# time-twister.net
KiCad netlist of a schematic drawn in EAGLE
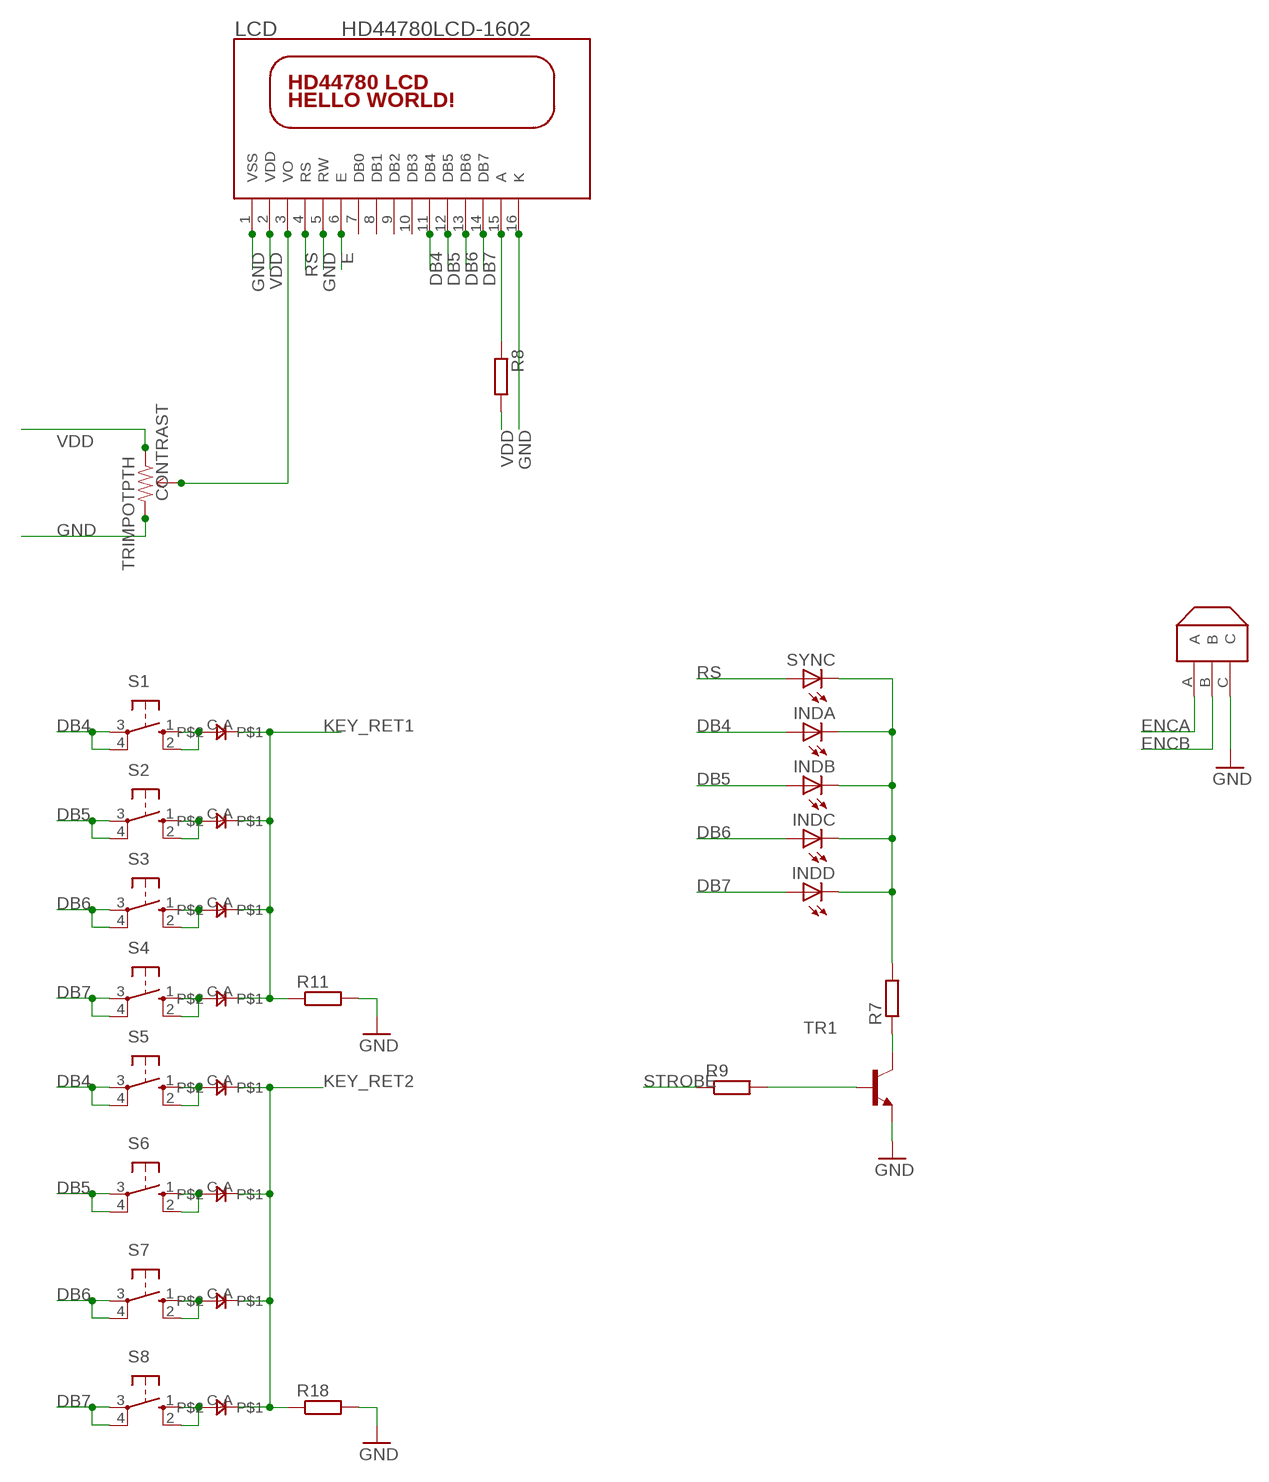
[diagram p0: schematic, sheet 1]
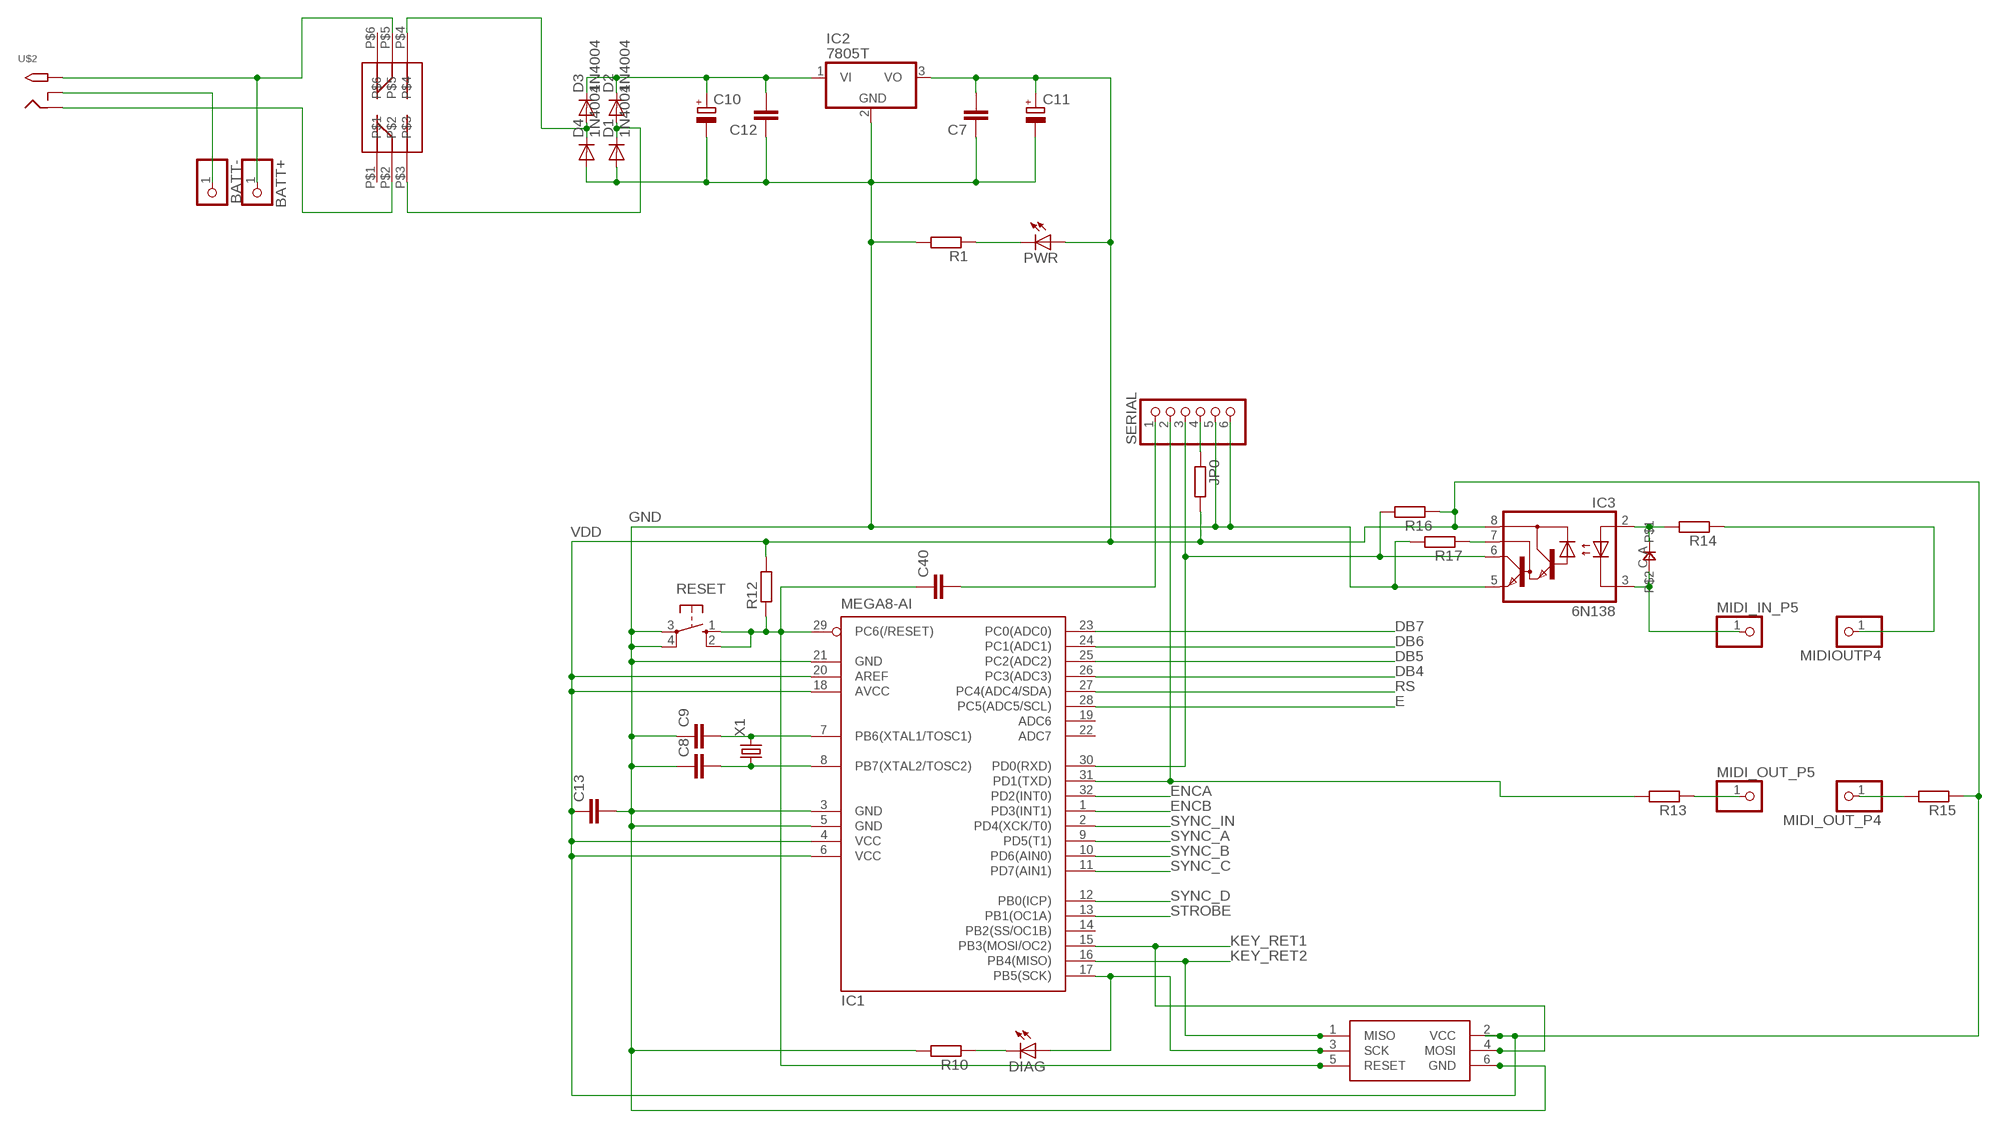
[diagram p1: schematic, sheet 2]
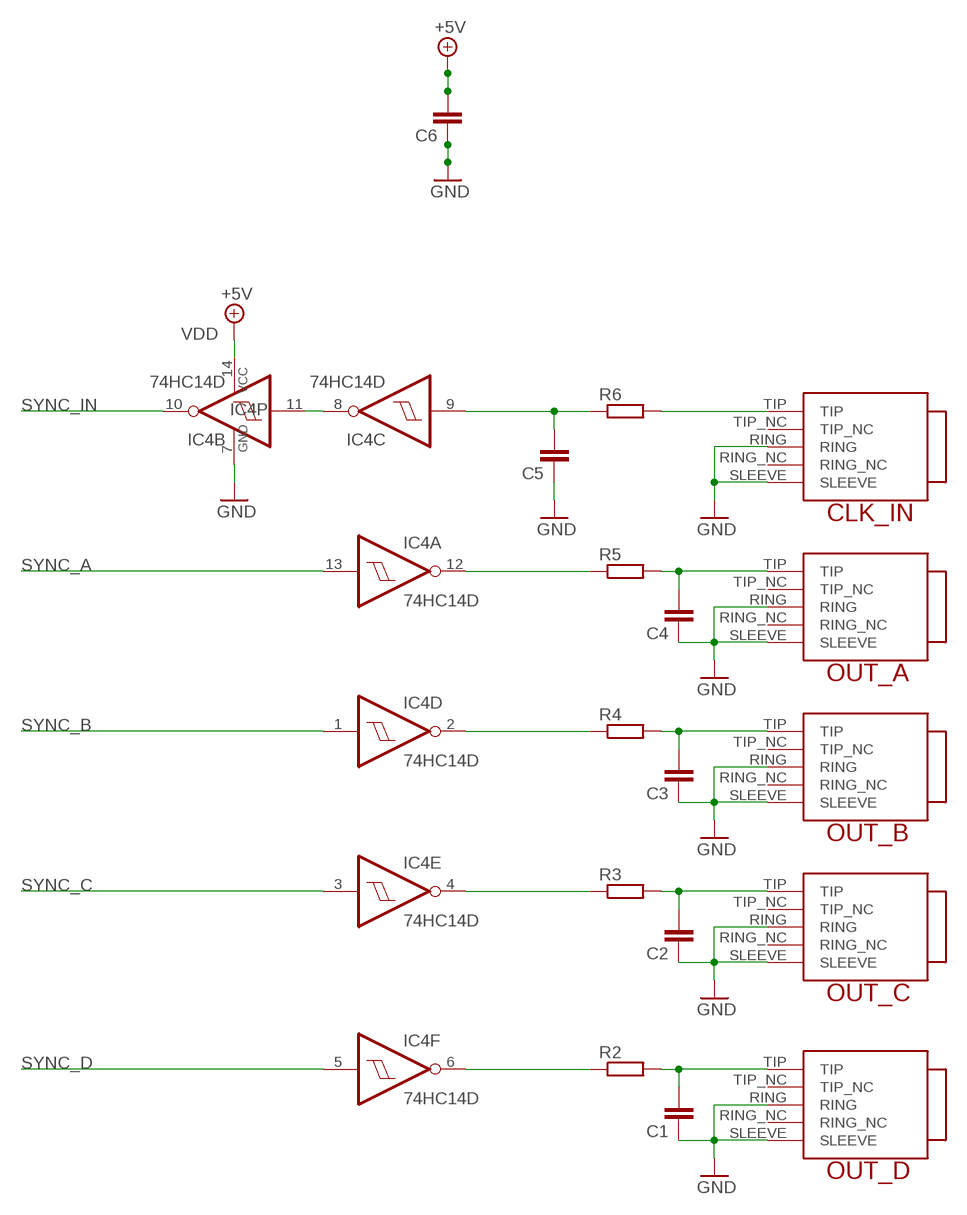
[diagram p2: schematic, sheet 3]

(export (version "E")
  (design (tool "Eeschema 10.0.6"))
  (components
    (comp (ref "C1")
      (value "C-EUC0805")
      (footprint "eagle-import:C0805")
      (libsource (lib "eagle-import") (part "C-EUC0805"))
    )
    (comp (ref "C2")
      (value "C-EUC0805")
      (footprint "eagle-import:C0805")
      (libsource (lib "eagle-import") (part "C-EUC0805"))
    )
    (comp (ref "C3")
      (value "C-EUC0805")
      (footprint "eagle-import:C0805")
      (libsource (lib "eagle-import") (part "C-EUC0805"))
    )
    (comp (ref "C4")
      (value "C-EUC0805")
      (footprint "eagle-import:C0805")
      (libsource (lib "eagle-import") (part "C-EUC0805"))
    )
    (comp (ref "C5")
      (value "C-EUC0805")
      (footprint "eagle-import:C0805")
      (libsource (lib "eagle-import") (part "C-EUC0805"))
    )
    (comp (ref "C6")
      (value "C-EUC0805")
      (footprint "eagle-import:C0805")
      (libsource (lib "eagle-import") (part "C-EUC0805"))
    )
    (comp (ref "CLK_IN")
      (value "TRUCONNECTJACK")
      (footprint "eagle-import:TRUCONNECTJACK")
      (libsource (lib "eagle-import") (part "TRUCONNECTJACK"))
    )
    (comp (ref "IC4")
      (value "74HC14D")
      (footprint "eagle-import:SO14")
      (libsource (lib "eagle-import") (part "7414DHC"))
    )
    (comp (ref "OUT_A")
      (value "TRUCONNECTJACK")
      (footprint "eagle-import:TRUCONNECTJACK")
      (libsource (lib "eagle-import") (part "TRUCONNECTJACK"))
    )
    (comp (ref "OUT_B")
      (value "TRUCONNECTJACK")
      (footprint "eagle-import:TRUCONNECTJACK")
      (libsource (lib "eagle-import") (part "TRUCONNECTJACK"))
    )
    (comp (ref "OUT_C")
      (value "TRUCONNECTJACK")
      (footprint "eagle-import:TRUCONNECTJACK")
      (libsource (lib "eagle-import") (part "TRUCONNECTJACK"))
    )
    (comp (ref "OUT_D")
      (value "TRUCONNECTJACK")
      (footprint "eagle-import:TRUCONNECTJACK")
      (libsource (lib "eagle-import") (part "TRUCONNECTJACK"))
    )
    (comp (ref "R2")
      (value "R-EU_M0805")
      (footprint "eagle-import:M0805")
      (libsource (lib "eagle-import") (part "R-EU_M0805"))
    )
    (comp (ref "R3")
      (value "R-EU_M0805")
      (footprint "eagle-import:M0805")
      (libsource (lib "eagle-import") (part "R-EU_M0805"))
    )
    (comp (ref "R4")
      (value "R-EU_M0805")
      (footprint "eagle-import:M0805")
      (libsource (lib "eagle-import") (part "R-EU_M0805"))
    )
    (comp (ref "R5")
      (value "R-EU_M0805")
      (footprint "eagle-import:M0805")
      (libsource (lib "eagle-import") (part "R-EU_M0805"))
    )
    (comp (ref "R6")
      (value "R-EU_M0805")
      (footprint "eagle-import:M0805")
      (libsource (lib "eagle-import") (part "R-EU_M0805"))
    )
    (comp (ref "CONTRAST")
      (value "TRIMPOTPTH")
      (footprint "eagle-import:TRIM_POT_PTH")
      (libsource (lib "eagle-import") (part "TRIMPOTPTH"))
    )
    (comp (ref "D5")
      (value "0805DIODE")
      (footprint "eagle-import:0805DIODE")
      (libsource (lib "eagle-import") (part "0805DIODE"))
    )
    (comp (ref "D6")
      (value "0805DIODE")
      (footprint "eagle-import:0805DIODE")
      (libsource (lib "eagle-import") (part "0805DIODE"))
    )
    (comp (ref "D7")
      (value "0805DIODE")
      (footprint "eagle-import:0805DIODE")
      (libsource (lib "eagle-import") (part "0805DIODE"))
    )
    (comp (ref "D8")
      (value "0805DIODE")
      (footprint "eagle-import:0805DIODE")
      (libsource (lib "eagle-import") (part "0805DIODE"))
    )
    (comp (ref "D10")
      (value "0805DIODE")
      (footprint "eagle-import:0805DIODE")
      (libsource (lib "eagle-import") (part "0805DIODE"))
    )
    (comp (ref "D11")
      (value "0805DIODE")
      (footprint "eagle-import:0805DIODE")
      (libsource (lib "eagle-import") (part "0805DIODE"))
    )
    (comp (ref "D12")
      (value "0805DIODE")
      (footprint "eagle-import:0805DIODE")
      (libsource (lib "eagle-import") (part "0805DIODE"))
    )
    (comp (ref "D13")
      (value "0805DIODE")
      (footprint "eagle-import:0805DIODE")
      (libsource (lib "eagle-import") (part "0805DIODE"))
    )
    (comp (ref "ENC1")
      (value "ENCODER")
      (footprint "eagle-import:ENCODER")
      (libsource (lib "eagle-import") (part "ENCODER"))
    )
    (comp (ref "INDA")
      (value "LED3MM")
      (footprint "eagle-import:LED3MM")
      (libsource (lib "eagle-import") (part "led_LED3MM"))
    )
    (comp (ref "INDB")
      (value "LED3MM")
      (footprint "eagle-import:LED3MM")
      (libsource (lib "eagle-import") (part "led_LED3MM"))
    )
    (comp (ref "INDC")
      (value "LED3MM")
      (footprint "eagle-import:LED3MM")
      (libsource (lib "eagle-import") (part "led_LED3MM"))
    )
    (comp (ref "INDD")
      (value "LED3MM")
      (footprint "eagle-import:LED3MM")
      (libsource (lib "eagle-import") (part "led_LED3MM"))
    )
    (comp (ref "LCD")
      (value "HD44780LCD-1602")
      (footprint "eagle-import:LCD1602")
      (libsource (lib "eagle-import") (part "HD44780LCD-1602"))
    )
    (comp (ref "R7")
      (value "R-EU_R0805")
      (footprint "eagle-import:R0805")
      (libsource (lib "eagle-import") (part "R-EU_R0805"))
    )
    (comp (ref "R8")
      (value "R-EU_R0805")
      (footprint "eagle-import:R0805")
      (libsource (lib "eagle-import") (part "R-EU_R0805"))
    )
    (comp (ref "R9")
      (value "R-EU_R0805")
      (footprint "eagle-import:R0805")
      (libsource (lib "eagle-import") (part "R-EU_R0805"))
    )
    (comp (ref "R11")
      (value "R-EU_R0805")
      (footprint "eagle-import:R0805")
      (libsource (lib "eagle-import") (part "R-EU_R0805"))
    )
    (comp (ref "R18")
      (value "R-EU_R0805")
      (footprint "eagle-import:R0805")
      (libsource (lib "eagle-import") (part "R-EU_R0805"))
    )
    (comp (ref "S1")
      (value "40-XX")
      (footprint "eagle-import:B3F-40XX")
      (fields (field (name "MF") "OMRON COMPONENTS USA") (field (name "MPN") "B3F-4000"))
      (libsource (lib "eagle-import") (part "40-XX"))
    )
    (comp (ref "S2")
      (value "40-XX")
      (footprint "eagle-import:B3F-40XX")
      (fields (field (name "MF") "OMRON COMPONENTS USA") (field (name "MPN") "B3F-4000"))
      (libsource (lib "eagle-import") (part "40-XX"))
    )
    (comp (ref "S3")
      (value "40-XX")
      (footprint "eagle-import:B3F-40XX")
      (fields (field (name "MF") "OMRON COMPONENTS USA") (field (name "MPN") "B3F-4000"))
      (libsource (lib "eagle-import") (part "40-XX"))
    )
    (comp (ref "S4")
      (value "40-XX")
      (footprint "eagle-import:B3F-40XX")
      (fields (field (name "MF") "OMRON COMPONENTS USA") (field (name "MPN") "B3F-4000"))
      (libsource (lib "eagle-import") (part "40-XX"))
    )
    (comp (ref "S5")
      (value "40-XX")
      (footprint "eagle-import:B3F-40XX")
      (fields (field (name "MF") "OMRON COMPONENTS USA") (field (name "MPN") "B3F-4000"))
      (libsource (lib "eagle-import") (part "40-XX"))
    )
    (comp (ref "S6")
      (value "40-XX")
      (footprint "eagle-import:B3F-40XX")
      (fields (field (name "MF") "OMRON COMPONENTS USA") (field (name "MPN") "B3F-4000"))
      (libsource (lib "eagle-import") (part "40-XX"))
    )
    (comp (ref "S7")
      (value "40-XX")
      (footprint "eagle-import:B3F-40XX")
      (fields (field (name "MF") "OMRON COMPONENTS USA") (field (name "MPN") "B3F-4000"))
      (libsource (lib "eagle-import") (part "40-XX"))
    )
    (comp (ref "S8")
      (value "40-XX")
      (footprint "eagle-import:B3F-40XX")
      (fields (field (name "MF") "OMRON COMPONENTS USA") (field (name "MPN") "B3F-4000"))
      (libsource (lib "eagle-import") (part "40-XX"))
    )
    (comp (ref "SYNC")
      (value "LED3MM")
      (footprint "eagle-import:LED3MM")
      (libsource (lib "eagle-import") (part "led_LED3MM"))
    )
    (comp (ref "TR1")
      (value "MMBT3904LT1-NPN-SOT23-BEC")
      (footprint "eagle-import:SOT23-BEC")
      (libsource (lib "eagle-import") (part "-NPN-SOT23-BECMMBT3904LT1"))
    )
    (comp (ref "BATT+")
      (value "HEADER-1X1")
      (footprint "eagle-import:1X01_OVAL")
      (libsource (lib "eagle-import") (part "HEADER-1X1"))
    )
    (comp (ref "BATT-")
      (value "HEADER-1X1")
      (footprint "eagle-import:1X01_OVAL")
      (libsource (lib "eagle-import") (part "HEADER-1X1"))
    )
    (comp (ref "C7")
      (value "C-EUC0805")
      (footprint "eagle-import:C0805")
      (libsource (lib "eagle-import") (part "C-EUC0805"))
    )
    (comp (ref "C8")
      (value "C-EUC0805")
      (footprint "eagle-import:C0805")
      (libsource (lib "eagle-import") (part "C-EUC0805"))
    )
    (comp (ref "C9")
      (value "C-EUC0805")
      (footprint "eagle-import:C0805")
      (libsource (lib "eagle-import") (part "C-EUC0805"))
    )
    (comp (ref "C10")
      (value "CPOL-EUE2.5-6")
      (footprint "eagle-import:E2,5-6")
      (libsource (lib "eagle-import") (part "CPOL-EUE2.5-6"))
    )
    (comp (ref "C11")
      (value "CPOL-EUE2.5-6")
      (footprint "eagle-import:E2,5-6")
      (libsource (lib "eagle-import") (part "CPOL-EUE2.5-6"))
    )
    (comp (ref "C12")
      (value "C-EUC0805")
      (footprint "eagle-import:C0805")
      (libsource (lib "eagle-import") (part "C-EUC0805"))
    )
    (comp (ref "C13")
      (value "C-EUC0805")
      (footprint "eagle-import:C0805")
      (libsource (lib "eagle-import") (part "C-EUC0805"))
    )
    (comp (ref "C40")
      (value "C-EUC0805")
      (footprint "eagle-import:C0805")
      (libsource (lib "eagle-import") (part "C-EUC0805"))
    )
    (comp (ref "D1")
      (value "1N4004")
      (footprint "eagle-import:DO-VERT")
      (libsource (lib "eagle-import") (part "1N4004"))
    )
    (comp (ref "D2")
      (value "1N4004")
      (footprint "eagle-import:DO-VERT")
      (libsource (lib "eagle-import") (part "1N4004"))
    )
    (comp (ref "D3")
      (value "1N4004")
      (footprint "eagle-import:DO-VERT")
      (libsource (lib "eagle-import") (part "1N4004"))
    )
    (comp (ref "D4")
      (value "1N4004")
      (footprint "eagle-import:DO-VERT")
      (libsource (lib "eagle-import") (part "1N4004"))
    )
    (comp (ref "D9")
      (value "0805DIODE")
      (footprint "eagle-import:0805DIODE")
      (libsource (lib "eagle-import") (part "0805DIODE"))
    )
    (comp (ref "DIAG")
      (value "LED3MM")
      (footprint "eagle-import:LED3MM")
      (libsource (lib "eagle-import") (part "led_LED3MM"))
    )
    (comp (ref "IC1")
      (value "MEGA8-AI")
      (footprint "eagle-import:TQFP32-08")
      (libsource (lib "eagle-import") (part "MEGA8-AI"))
    )
    (comp (ref "IC2")
      (value "7805T")
      (footprint "eagle-import:TO220H")
      (libsource (lib "eagle-import") (part "78T05"))
    )
    (comp (ref "IC3")
      (value "6N138")
      (footprint "eagle-import:DIL08")
      (libsource (lib "eagle-import") (part "6N138"))
    )
    (comp (ref "JP0")
      (value "R-EU_R0805")
      (footprint "eagle-import:R0805")
      (libsource (lib "eagle-import") (part "R-EU_R0805"))
    )
    (comp (ref "MIDIOUTP4")
      (value "HEADER-1X1")
      (footprint "eagle-import:1X01_OVAL")
      (libsource (lib "eagle-import") (part "HEADER-1X1"))
    )
    (comp (ref "MIDI_IN_P5")
      (value "HEADER-1X1")
      (footprint "eagle-import:1X01_OVAL")
      (libsource (lib "eagle-import") (part "HEADER-1X1"))
    )
    (comp (ref "MIDI_OUT_P4")
      (value "HEADER-1X1")
      (footprint "eagle-import:1X01_OVAL")
      (libsource (lib "eagle-import") (part "HEADER-1X1"))
    )
    (comp (ref "MIDI_OUT_P5")
      (value "HEADER-1X1")
      (footprint "eagle-import:1X01_OVAL")
      (libsource (lib "eagle-import") (part "HEADER-1X1"))
    )
    (comp (ref "ONOFF")
      (value "2P2T_LATCHING")
      (footprint "eagle-import:2P2T_LATCHING")
      (libsource (lib "eagle-import") (part "2P2T_LATCHING"))
    )
    (comp (ref "PWR")
      (value "LED3MM")
      (footprint "eagle-import:LED3MM")
      (libsource (lib "eagle-import") (part "LED3MM"))
    )
    (comp (ref "R1")
      (value "R-EU_R0805")
      (footprint "eagle-import:R0805")
      (libsource (lib "eagle-import") (part "R-EU_R0805"))
    )
    (comp (ref "R10")
      (value "R-EU_R0805")
      (footprint "eagle-import:R0805")
      (libsource (lib "eagle-import") (part "R-EU_R0805"))
    )
    (comp (ref "R12")
      (value "R-EU_R0805")
      (footprint "eagle-import:R0805")
      (libsource (lib "eagle-import") (part "R-EU_R0805"))
    )
    (comp (ref "R13")
      (value "R-EU_R0805")
      (footprint "eagle-import:R0805")
      (libsource (lib "eagle-import") (part "R-EU_R0805"))
    )
    (comp (ref "R14")
      (value "R-EU_R0805")
      (footprint "eagle-import:R0805")
      (libsource (lib "eagle-import") (part "R-EU_R0805"))
    )
    (comp (ref "R15")
      (value "R-EU_R0805")
      (footprint "eagle-import:R0805")
      (libsource (lib "eagle-import") (part "R-EU_R0805"))
    )
    (comp (ref "R16")
      (value "R-EU_R0805")
      (footprint "eagle-import:R0805")
      (libsource (lib "eagle-import") (part "R-EU_R0805"))
    )
    (comp (ref "R17")
      (value "R-EU_R0805")
      (footprint "eagle-import:R0805")
      (libsource (lib "eagle-import") (part "R-EU_R0805"))
    )
    (comp (ref "RESET")
      (value "10-XX")
      (footprint "eagle-import:B3F-10XX")
      (fields (field (name "MPN") "B3F-1000"))
      (libsource (lib "eagle-import") (part "10-XX"))
    )
    (comp (ref "SERIAL")
      (value "PINHD-1X6")
      (footprint "eagle-import:1X06")
      (libsource (lib "eagle-import") (part "PINHD-1X6"))
    )
    (comp (ref "U$2")
      (value "2.1MMJACKTHM")
      (footprint "eagle-import:PJ-102A")
      (libsource (lib "eagle-import") (part "2.1MMJACKTHM"))
    )
    (comp (ref "U$34")
      (value "TAG_CONN_AVR")
      (footprint "eagle-import:TC2030-MCP-NL")
      (libsource (lib "eagle-import") (part "TAG_CONN_AVR"))
    )
    (comp (ref "X1")
      (value "CRYSTALHC49S")
      (footprint "eagle-import:HC49_S")
      (libsource (lib "eagle-import") (part "CRYSTALHC49S"))
    )
  )
  (nets
    (net (code "1") (name "DB4") (class "Default")
      (node (ref "IC1") (pin "26") (pinfunction "PC3(ADC3)_26") (pintype "bidirectional"))
      (node (ref "INDA") (pin "A") (pinfunction "A_A") (pintype "passive"))
      (node (ref "LCD") (pin "11") (pinfunction "DB4_11") (pintype "bidirectional"))
      (node (ref "S1") (pin "3") (pinfunction "P_3") (pintype "passive"))
      (node (ref "S1") (pin "4") (pinfunction "P1_4") (pintype "passive"))
      (node (ref "S5") (pin "3") (pinfunction "P_3") (pintype "passive"))
      (node (ref "S5") (pin "4") (pinfunction "P1_4") (pintype "passive"))
    )
    (net (code "2") (name "DB5") (class "Default")
      (node (ref "IC1") (pin "25") (pinfunction "PC2(ADC2)_25") (pintype "bidirectional"))
      (node (ref "INDB") (pin "A") (pinfunction "A_A") (pintype "passive"))
      (node (ref "LCD") (pin "12") (pinfunction "DB5_12") (pintype "bidirectional"))
      (node (ref "S2") (pin "3") (pinfunction "P_3") (pintype "passive"))
      (node (ref "S2") (pin "4") (pinfunction "P1_4") (pintype "passive"))
      (node (ref "S6") (pin "3") (pinfunction "P_3") (pintype "passive"))
      (node (ref "S6") (pin "4") (pinfunction "P1_4") (pintype "passive"))
    )
    (net (code "3") (name "DB6") (class "Default")
      (node (ref "IC1") (pin "24") (pinfunction "PC1(ADC1)_24") (pintype "bidirectional"))
      (node (ref "INDC") (pin "A") (pinfunction "A_A") (pintype "passive"))
      (node (ref "LCD") (pin "13") (pinfunction "DB6_13") (pintype "bidirectional"))
      (node (ref "S3") (pin "3") (pinfunction "P_3") (pintype "passive"))
      (node (ref "S3") (pin "4") (pinfunction "P1_4") (pintype "passive"))
      (node (ref "S7") (pin "3") (pinfunction "P_3") (pintype "passive"))
      (node (ref "S7") (pin "4") (pinfunction "P1_4") (pintype "passive"))
    )
    (net (code "4") (name "DB7") (class "Default")
      (node (ref "IC1") (pin "23") (pinfunction "PC0(ADC0)_23") (pintype "bidirectional"))
      (node (ref "INDD") (pin "A") (pinfunction "A_A") (pintype "passive"))
      (node (ref "LCD") (pin "14") (pinfunction "DB7_14") (pintype "bidirectional"))
      (node (ref "S4") (pin "3") (pinfunction "P_3") (pintype "passive"))
      (node (ref "S4") (pin "4") (pinfunction "P1_4") (pintype "passive"))
      (node (ref "S8") (pin "3") (pinfunction "P_3") (pintype "passive"))
      (node (ref "S8") (pin "4") (pinfunction "P1_4") (pintype "passive"))
    )
    (net (code "5") (name "E") (class "Default")
      (node (ref "IC1") (pin "28") (pinfunction "PC5(ADC5/SCL)_28") (pintype "bidirectional"))
      (node (ref "LCD") (pin "6") (pinfunction "E_6") (pintype "input"))
    )
    (net (code "6") (name "ENCA") (class "Default")
      (node (ref "ENC1") (pin "A") (pinfunction "A_A") (pintype "bidirectional"))
      (node (ref "IC1") (pin "32") (pinfunction "PD2(INT0)_32") (pintype "bidirectional"))
    )
    (net (code "7") (name "ENCB") (class "Default")
      (node (ref "ENC1") (pin "B") (pinfunction "B_B") (pintype "bidirectional"))
      (node (ref "IC1") (pin "1") (pinfunction "PD3(INT1)_1") (pintype "bidirectional"))
    )
    (net (code "8") (name "GND") (class "Default")
      (node (ref "C1") (pin "1") (pinfunction "1_1") (pintype "passive"))
      (node (ref "C10") (pin "-") (pinfunction "-_-") (pintype "passive"))
      (node (ref "C11") (pin "-") (pinfunction "-_-") (pintype "passive"))
      (node (ref "C12") (pin "1") (pinfunction "1_1") (pintype "passive"))
      (node (ref "C13") (pin "2") (pinfunction "2_2") (pintype "passive"))
      (node (ref "C2") (pin "1") (pinfunction "1_1") (pintype "passive"))
      (node (ref "C3") (pin "1") (pinfunction "1_1") (pintype "passive"))
      (node (ref "C4") (pin "1") (pinfunction "1_1") (pintype "passive"))
      (node (ref "C5") (pin "1") (pinfunction "1_1") (pintype "passive"))
      (node (ref "C6") (pin "1") (pinfunction "1_1") (pintype "passive"))
      (node (ref "C7") (pin "1") (pinfunction "1_1") (pintype "passive"))
      (node (ref "C8") (pin "1") (pinfunction "1_1") (pintype "passive"))
      (node (ref "C9") (pin "1") (pinfunction "1_1") (pintype "passive"))
      (node (ref "CLK_IN") (pin "RING") (pinfunction "RING_RING") (pintype "bidirectional"))
      (node (ref "CLK_IN") (pin "SLEEVE") (pinfunction "SLEEVE_SLEEVE") (pintype "bidirectional"))
      (node (ref "CONTRAST") (pin "3") (pinfunction "CW_3") (pintype "passive"))
      (node (ref "D1") (pin "A") (pinfunction "A_A") (pintype "passive"))
      (node (ref "D4") (pin "A") (pinfunction "A_A") (pintype "passive"))
      (node (ref "ENC1") (pin "C") (pinfunction "C_C") (pintype "bidirectional"))
      (node (ref "IC1") (pin "21") (pinfunction "GND_21") (pintype "power_in"))
      (node (ref "IC1") (pin "3") (pinfunction "GND_3") (pintype "power_in"))
      (node (ref "IC1") (pin "5") (pinfunction "GND_5") (pintype "power_in"))
      (node (ref "IC2") (pin "2") (pinfunction "GND_2") (pintype "passive"))
      (node (ref "IC3") (pin "5") (pinfunction "GND_5") (pintype "passive"))
      (node (ref "IC4") (pin "7") (pinfunction "GND_7") (pintype "power_in"))
      (node (ref "LCD") (pin "1") (pinfunction "VSS_1") (pintype "power_in"))
      (node (ref "LCD") (pin "16") (pinfunction "K_16") (pintype "input"))
      (node (ref "LCD") (pin "5") (pinfunction "RW_5") (pintype "input"))
      (node (ref "OUT_A") (pin "RING") (pinfunction "RING_RING") (pintype "bidirectional"))
      (node (ref "OUT_A") (pin "SLEEVE") (pinfunction "SLEEVE_SLEEVE") (pintype "bidirectional"))
      (node (ref "OUT_B") (pin "RING") (pinfunction "RING_RING") (pintype "bidirectional"))
      (node (ref "OUT_B") (pin "SLEEVE") (pinfunction "SLEEVE_SLEEVE") (pintype "bidirectional"))
      (node (ref "OUT_C") (pin "RING") (pinfunction "RING_RING") (pintype "bidirectional"))
      (node (ref "OUT_C") (pin "SLEEVE") (pinfunction "SLEEVE_SLEEVE") (pintype "bidirectional"))
      (node (ref "OUT_D") (pin "RING") (pinfunction "RING_RING") (pintype "bidirectional"))
      (node (ref "OUT_D") (pin "SLEEVE") (pinfunction "SLEEVE_SLEEVE") (pintype "bidirectional"))
      (node (ref "R1") (pin "2") (pinfunction "2_2") (pintype "passive"))
      (node (ref "R10") (pin "2") (pinfunction "2_2") (pintype "passive"))
      (node (ref "R11") (pin "2") (pinfunction "2_2") (pintype "passive"))
      (node (ref "R17") (pin "2") (pinfunction "2_2") (pintype "passive"))
      (node (ref "R18") (pin "2") (pinfunction "2_2") (pintype "passive"))
      (node (ref "RESET") (pin "3") (pinfunction "P_3") (pintype "passive"))
      (node (ref "RESET") (pin "4") (pinfunction "P1_4") (pintype "passive"))
      (node (ref "SERIAL") (pin "5") (pinfunction "5_5") (pintype "passive"))
      (node (ref "SERIAL") (pin "6") (pinfunction "6_6") (pintype "passive"))
      (node (ref "TR1") (pin "E") (pinfunction "E_E") (pintype "passive"))
      (node (ref "U$34") (pin "6") (pinfunction "GND_6") (pintype "power_in"))
    )
    (net (code "9") (name "KEY_RET1") (class "Default")
      (node (ref "D10") (pin "A") (pinfunction "P$2_A") (pintype "bidirectional"))
      (node (ref "D11") (pin "A") (pinfunction "P$2_A") (pintype "bidirectional"))
      (node (ref "D12") (pin "A") (pinfunction "P$2_A") (pintype "bidirectional"))
      (node (ref "D13") (pin "A") (pinfunction "P$2_A") (pintype "bidirectional"))
      (node (ref "IC1") (pin "15") (pinfunction "PB3(MOSI/OC2)_15") (pintype "bidirectional"))
      (node (ref "R11") (pin "1") (pinfunction "1_1") (pintype "passive"))
      (node (ref "U$34") (pin "4") (pinfunction "MOSI_4") (pintype "bidirectional"))
    )
    (net (code "10") (name "KEY_RET2") (class "Default")
      (node (ref "D5") (pin "A") (pinfunction "P$2_A") (pintype "bidirectional"))
      (node (ref "D6") (pin "A") (pinfunction "P$2_A") (pintype "bidirectional"))
      (node (ref "D7") (pin "A") (pinfunction "P$2_A") (pintype "bidirectional"))
      (node (ref "D8") (pin "A") (pinfunction "P$2_A") (pintype "bidirectional"))
      (node (ref "IC1") (pin "16") (pinfunction "PB4(MISO)_16") (pintype "bidirectional"))
      (node (ref "R18") (pin "1") (pinfunction "1_1") (pintype "passive"))
      (node (ref "U$34") (pin "1") (pinfunction "MISO_1") (pintype "bidirectional"))
    )
    (net (code "11") (name "Net-(BATT+-Pad1)") (class "Default")
      (node (ref "BATT+") (pin "1") (pinfunction "1_1") (pintype "passive"))
      (node (ref "ONOFF") (pin "P$5") (pinfunction "P$5_P$5") (pintype "bidirectional"))
      (node (ref "U$2") (pin "TIP") (pinfunction "TIP_TIP") (pintype "bidirectional"))
    )
    (net (code "12") (name "Net-(BATT--Pad1)") (class "Default")
      (node (ref "BATT-") (pin "1") (pinfunction "1_1") (pintype "passive"))
      (node (ref "U$2") (pin "RING_SW") (pinfunction "RING_SW_RING_SW") (pintype "bidirectional"))
    )
    (net (code "13") (name "Net-(C1-Pad2)") (class "Default")
      (node (ref "C1") (pin "2") (pinfunction "2_2") (pintype "passive"))
      (node (ref "OUT_D") (pin "TIP") (pinfunction "TIP_TIP") (pintype "bidirectional"))
      (node (ref "R2") (pin "2") (pinfunction "2_2") (pintype "passive"))
    )
    (net (code "14") (name "Net-(C2-Pad2)") (class "Default")
      (node (ref "C2") (pin "2") (pinfunction "2_2") (pintype "passive"))
      (node (ref "OUT_C") (pin "TIP") (pinfunction "TIP_TIP") (pintype "bidirectional"))
      (node (ref "R3") (pin "2") (pinfunction "2_2") (pintype "passive"))
    )
    (net (code "15") (name "Net-(C3-Pad2)") (class "Default")
      (node (ref "C3") (pin "2") (pinfunction "2_2") (pintype "passive"))
      (node (ref "OUT_B") (pin "TIP") (pinfunction "TIP_TIP") (pintype "bidirectional"))
      (node (ref "R4") (pin "2") (pinfunction "2_2") (pintype "passive"))
    )
    (net (code "16") (name "Net-(C4-Pad2)") (class "Default")
      (node (ref "C4") (pin "2") (pinfunction "2_2") (pintype "passive"))
      (node (ref "OUT_A") (pin "TIP") (pinfunction "TIP_TIP") (pintype "bidirectional"))
      (node (ref "R5") (pin "2") (pinfunction "2_2") (pintype "passive"))
    )
    (net (code "17") (name "Net-(C40-Pad2)") (class "Default")
      (node (ref "C40") (pin "2") (pinfunction "2_2") (pintype "passive"))
      (node (ref "SERIAL") (pin "1") (pinfunction "1_1") (pintype "passive"))
    )
    (net (code "18") (name "Net-(CLK_IN-PadTIP)") (class "Default")
      (node (ref "CLK_IN") (pin "TIP") (pinfunction "TIP_TIP") (pintype "bidirectional"))
      (node (ref "R6") (pin "2") (pinfunction "2_2") (pintype "passive"))
    )
    (net (code "19") (name "Net-(CONTRAST-WIPER)") (class "Default")
      (node (ref "CONTRAST") (pin "2") (pinfunction "WIPER_2") (pintype "passive"))
      (node (ref "LCD") (pin "3") (pinfunction "VO_3") (pintype "input"))
    )
    (net (code "20") (name "Net-(D1-PadC)") (class "Default")
      (node (ref "D1") (pin "C") (pinfunction "C_C") (pintype "passive"))
      (node (ref "D2") (pin "A") (pinfunction "A_A") (pintype "passive"))
      (node (ref "ONOFF") (pin "P$3") (pinfunction "P$3_P$3") (pintype "bidirectional"))
    )
    (net (code "21") (name "Net-(D3-PadA)") (class "Default")
      (node (ref "D3") (pin "A") (pinfunction "A_A") (pintype "passive"))
      (node (ref "D4") (pin "C") (pinfunction "C_C") (pintype "passive"))
      (node (ref "ONOFF") (pin "P$4") (pinfunction "P$4_P$4") (pintype "bidirectional"))
    )
    (net (code "22") (name "Net-(D5-P$1)") (class "Default")
      (node (ref "D5") (pin "C") (pinfunction "P$1_C") (pintype "bidirectional"))
      (node (ref "S8") (pin "1") (pinfunction "S_1") (pintype "passive"))
      (node (ref "S8") (pin "2") (pinfunction "S1_2") (pintype "passive"))
    )
    (net (code "23") (name "Net-(D6-P$1)") (class "Default")
      (node (ref "D6") (pin "C") (pinfunction "P$1_C") (pintype "bidirectional"))
      (node (ref "S7") (pin "1") (pinfunction "S_1") (pintype "passive"))
      (node (ref "S7") (pin "2") (pinfunction "S1_2") (pintype "passive"))
    )
    (net (code "24") (name "Net-(D7-P$1)") (class "Default")
      (node (ref "D7") (pin "C") (pinfunction "P$1_C") (pintype "bidirectional"))
      (node (ref "S6") (pin "1") (pinfunction "S_1") (pintype "passive"))
      (node (ref "S6") (pin "2") (pinfunction "S1_2") (pintype "passive"))
    )
    (net (code "25") (name "Net-(D8-P$1)") (class "Default")
      (node (ref "D8") (pin "C") (pinfunction "P$1_C") (pintype "bidirectional"))
      (node (ref "S5") (pin "1") (pinfunction "S_1") (pintype "passive"))
      (node (ref "S5") (pin "2") (pinfunction "S1_2") (pintype "passive"))
    )
    (net (code "26") (name "Net-(D9-P$1)") (class "Default")
      (node (ref "D9") (pin "C") (pinfunction "P$1_C") (pintype "bidirectional"))
      (node (ref "IC3") (pin "3") (pinfunction "C_3") (pintype "passive"))
      (node (ref "MIDI_IN_P5") (pin "1") (pinfunction "1_1") (pintype "passive"))
    )
    (net (code "27") (name "Net-(D9-P$2)") (class "Default")
      (node (ref "D9") (pin "A") (pinfunction "P$2_A") (pintype "bidirectional"))
      (node (ref "IC3") (pin "2") (pinfunction "A_2") (pintype "passive"))
      (node (ref "R14") (pin "2") (pinfunction "2_2") (pintype "passive"))
    )
    (net (code "28") (name "Net-(D10-P$1)") (class "Default")
      (node (ref "D10") (pin "C") (pinfunction "P$1_C") (pintype "bidirectional"))
      (node (ref "S2") (pin "1") (pinfunction "S_1") (pintype "passive"))
      (node (ref "S2") (pin "2") (pinfunction "S1_2") (pintype "passive"))
    )
    (net (code "29") (name "Net-(D11-P$1)") (class "Default")
      (node (ref "D11") (pin "C") (pinfunction "P$1_C") (pintype "bidirectional"))
      (node (ref "S4") (pin "1") (pinfunction "S_1") (pintype "passive"))
      (node (ref "S4") (pin "2") (pinfunction "S1_2") (pintype "passive"))
    )
    (net (code "30") (name "Net-(D12-P$1)") (class "Default")
      (node (ref "D12") (pin "C") (pinfunction "P$1_C") (pintype "bidirectional"))
      (node (ref "S1") (pin "1") (pinfunction "S_1") (pintype "passive"))
      (node (ref "S1") (pin "2") (pinfunction "S1_2") (pintype "passive"))
    )
    (net (code "31") (name "Net-(D13-P$1)") (class "Default")
      (node (ref "D13") (pin "C") (pinfunction "P$1_C") (pintype "bidirectional"))
      (node (ref "S3") (pin "1") (pinfunction "S_1") (pintype "passive"))
      (node (ref "S3") (pin "2") (pinfunction "S1_2") (pintype "passive"))
    )
    (net (code "32") (name "Net-(DIAG-C)") (class "Default")
      (node (ref "DIAG") (pin "K") (pinfunction "C_K") (pintype "passive"))
      (node (ref "R10") (pin "1") (pinfunction "1_1") (pintype "passive"))
    )
    (net (code "33") (name "Net-(IC1-PB5(SCK))") (class "Default")
      (node (ref "DIAG") (pin "A") (pinfunction "A_A") (pintype "passive"))
      (node (ref "IC1") (pin "17") (pinfunction "PB5(SCK)_17") (pintype "bidirectional"))
      (node (ref "U$34") (pin "3") (pinfunction "SCK_3") (pintype "bidirectional"))
    )
    (net (code "34") (name "Net-(IC1-PB6(XTAL1{slash}TOSC1))") (class "Default")
      (node (ref "C9") (pin "2") (pinfunction "2_2") (pintype "passive"))
      (node (ref "IC1") (pin "7") (pinfunction "PB6(XTAL1/TOSC1)_7") (pintype "bidirectional"))
      (node (ref "X1") (pin "2") (pinfunction "2_2") (pintype "passive"))
    )
    (net (code "35") (name "Net-(IC1-PB7(XTAL2{slash}TOSC2))") (class "Default")
      (node (ref "C8") (pin "2") (pinfunction "2_2") (pintype "passive"))
      (node (ref "IC1") (pin "8") (pinfunction "PB7(XTAL2/TOSC2)_8") (pintype "bidirectional"))
      (node (ref "X1") (pin "1") (pinfunction "1_1") (pintype "passive"))
    )
    (net (code "36") (name "Net-(IC1-PC6({slash}RESET))") (class "Default")
      (node (ref "C40") (pin "1") (pinfunction "1_1") (pintype "passive"))
      (node (ref "IC1") (pin "29") (pinfunction "PC6(/RESET)_29") (pintype "bidirectional"))
      (node (ref "R12") (pin "1") (pinfunction "1_1") (pintype "passive"))
      (node (ref "RESET") (pin "1") (pinfunction "S_1") (pintype "passive"))
      (node (ref "RESET") (pin "2") (pinfunction "S1_2") (pintype "passive"))
      (node (ref "U$34") (pin "5") (pinfunction "RESET_5") (pintype "bidirectional"))
    )
    (net (code "37") (name "Net-(IC1-PD0(RXD))") (class "Default")
      (node (ref "IC1") (pin "30") (pinfunction "PD0(RXD)_30") (pintype "bidirectional"))
      (node (ref "IC3") (pin "6") (pinfunction "VO_6") (pintype "passive"))
      (node (ref "R16") (pin "2") (pinfunction "2_2") (pintype "passive"))
      (node (ref "SERIAL") (pin "3") (pinfunction "3_3") (pintype "passive"))
    )
    (net (code "38") (name "Net-(IC1-PD1(TXD))") (class "Default")
      (node (ref "IC1") (pin "31") (pinfunction "PD1(TXD)_31") (pintype "bidirectional"))
      (node (ref "R13") (pin "2") (pinfunction "2_2") (pintype "passive"))
      (node (ref "SERIAL") (pin "2") (pinfunction "2_2") (pintype "passive"))
    )
    (net (code "39") (name "Net-(IC2-VI)") (class "Default")
      (node (ref "C10") (pin "+") (pinfunction "+_+") (pintype "passive"))
      (node (ref "C12") (pin "2") (pinfunction "2_2") (pintype "passive"))
      (node (ref "D2") (pin "C") (pinfunction "C_C") (pintype "passive"))
      (node (ref "D3") (pin "C") (pinfunction "C_C") (pintype "passive"))
      (node (ref "IC2") (pin "1") (pinfunction "VI_1") (pintype "input"))
    )
    (net (code "40") (name "Net-(IC3-VB)") (class "Default")
      (node (ref "IC3") (pin "7") (pinfunction "VB_7") (pintype "passive"))
      (node (ref "R17") (pin "1") (pinfunction "1_1") (pintype "passive"))
    )
    (net (code "41") (name "Net-(IC4A-O)") (class "Default")
      (node (ref "IC4") (pin "12") (pinfunction "O_12") (pintype "output"))
      (node (ref "R5") (pin "1") (pinfunction "1_1") (pintype "passive"))
    )
    (net (code "42") (name "Net-(IC4B-I)") (class "Default")
      (node (ref "IC4") (pin "11") (pinfunction "I_11") (pintype "input"))
      (node (ref "IC4") (pin "8") (pinfunction "O_8") (pintype "output"))
    )
    (net (code "43") (name "Net-(IC4C-I)") (class "Default")
      (node (ref "C5") (pin "2") (pinfunction "2_2") (pintype "passive"))
      (node (ref "IC4") (pin "9") (pinfunction "I_9") (pintype "input"))
      (node (ref "R6") (pin "1") (pinfunction "1_1") (pintype "passive"))
    )
    (net (code "44") (name "Net-(IC4D-O)") (class "Default")
      (node (ref "IC4") (pin "2") (pinfunction "O_2") (pintype "output"))
      (node (ref "R4") (pin "1") (pinfunction "1_1") (pintype "passive"))
    )
    (net (code "45") (name "Net-(IC4E-O)") (class "Default")
      (node (ref "IC4") (pin "4") (pinfunction "O_4") (pintype "output"))
      (node (ref "R3") (pin "1") (pinfunction "1_1") (pintype "passive"))
    )
    (net (code "46") (name "Net-(IC4F-O)") (class "Default")
      (node (ref "IC4") (pin "6") (pinfunction "O_6") (pintype "output"))
      (node (ref "R2") (pin "1") (pinfunction "1_1") (pintype "passive"))
    )
    (net (code "47") (name "Net-(INDA-C)") (class "Default")
      (node (ref "INDA") (pin "K") (pinfunction "C_K") (pintype "passive"))
      (node (ref "INDB") (pin "K") (pinfunction "C_K") (pintype "passive"))
      (node (ref "INDC") (pin "K") (pinfunction "C_K") (pintype "passive"))
      (node (ref "INDD") (pin "K") (pinfunction "C_K") (pintype "passive"))
      (node (ref "R7") (pin "2") (pinfunction "2_2") (pintype "passive"))
      (node (ref "SYNC") (pin "K") (pinfunction "C_K") (pintype "passive"))
    )
    (net (code "48") (name "Net-(JP0-Pad1)") (class "Default")
      (node (ref "JP0") (pin "1") (pinfunction "1_1") (pintype "passive"))
      (node (ref "SERIAL") (pin "4") (pinfunction "4_4") (pintype "passive"))
    )
    (net (code "49") (name "Net-(LCD-A)") (class "Default")
      (node (ref "LCD") (pin "15") (pinfunction "A_15") (pintype "input"))
      (node (ref "R8") (pin "1") (pinfunction "1_1") (pintype "passive"))
    )
    (net (code "50") (name "Net-(MIDIOUTP4-Pad1)") (class "Default")
      (node (ref "MIDIOUTP4") (pin "1") (pinfunction "1_1") (pintype "passive"))
      (node (ref "R14") (pin "1") (pinfunction "1_1") (pintype "passive"))
    )
    (net (code "51") (name "Net-(MIDI_OUT_P4-Pad1)") (class "Default")
      (node (ref "MIDI_OUT_P4") (pin "1") (pinfunction "1_1") (pintype "passive"))
      (node (ref "R15") (pin "2") (pinfunction "2_2") (pintype "passive"))
    )
    (net (code "52") (name "Net-(MIDI_OUT_P5-Pad1)") (class "Default")
      (node (ref "MIDI_OUT_P5") (pin "1") (pinfunction "1_1") (pintype "passive"))
      (node (ref "R13") (pin "1") (pinfunction "1_1") (pintype "passive"))
    )
    (net (code "53") (name "Net-(ONOFF-PadP$2)") (class "Default")
      (node (ref "ONOFF") (pin "P$2") (pinfunction "P$2_P$2") (pintype "bidirectional"))
      (node (ref "U$2") (pin "RING") (pinfunction "RING_RING") (pintype "bidirectional"))
    )
    (net (code "54") (name "Net-(PWR-C)") (class "Default")
      (node (ref "PWR") (pin "K") (pinfunction "C_K") (pintype "passive"))
      (node (ref "R1") (pin "1") (pinfunction "1_1") (pintype "passive"))
    )
    (net (code "55") (name "Net-(R7-Pad1)") (class "Default")
      (node (ref "R7") (pin "1") (pinfunction "1_1") (pintype "passive"))
      (node (ref "TR1") (pin "C") (pinfunction "C_C") (pintype "passive"))
    )
    (net (code "56") (name "Net-(R9-Pad2)") (class "Default")
      (node (ref "R9") (pin "2") (pinfunction "2_2") (pintype "passive"))
      (node (ref "TR1") (pin "B") (pinfunction "B_B") (pintype "passive"))
    )
    (net (code "57") (name "RS") (class "Default")
      (node (ref "IC1") (pin "27") (pinfunction "PC4(ADC4/SDA)_27") (pintype "bidirectional"))
      (node (ref "LCD") (pin "4") (pinfunction "RS_4") (pintype "input"))
      (node (ref "SYNC") (pin "A") (pinfunction "A_A") (pintype "passive"))
    )
    (net (code "58") (name "STROBE") (class "Default")
      (node (ref "IC1") (pin "13") (pinfunction "PB1(OC1A)_13") (pintype "bidirectional"))
      (node (ref "R9") (pin "1") (pinfunction "1_1") (pintype "passive"))
    )
    (net (code "59") (name "SYNC_A") (class "Default")
      (node (ref "IC1") (pin "9") (pinfunction "PD5(T1)_9") (pintype "bidirectional"))
      (node (ref "IC4") (pin "13") (pinfunction "I_13") (pintype "input"))
    )
    (net (code "60") (name "SYNC_B") (class "Default")
      (node (ref "IC1") (pin "10") (pinfunction "PD6(AIN0)_10") (pintype "bidirectional"))
      (node (ref "IC4") (pin "1") (pinfunction "I_1") (pintype "input"))
    )
    (net (code "61") (name "SYNC_C") (class "Default")
      (node (ref "IC1") (pin "11") (pinfunction "PD7(AIN1)_11") (pintype "bidirectional"))
      (node (ref "IC4") (pin "3") (pinfunction "I_3") (pintype "input"))
    )
    (net (code "62") (name "SYNC_D") (class "Default")
      (node (ref "IC1") (pin "12") (pinfunction "PB0(ICP)_12") (pintype "bidirectional"))
      (node (ref "IC4") (pin "5") (pinfunction "I_5") (pintype "input"))
    )
    (net (code "63") (name "SYNC_IN") (class "Default")
      (node (ref "IC1") (pin "2") (pinfunction "PD4(XCK/T0)_2") (pintype "bidirectional"))
      (node (ref "IC4") (pin "10") (pinfunction "O_10") (pintype "output"))
    )
    (net (code "64") (name "VDD") (class "Default")
      (node (ref "C11") (pin "+") (pinfunction "+_+") (pintype "passive"))
      (node (ref "C13") (pin "1") (pinfunction "1_1") (pintype "passive"))
      (node (ref "C6") (pin "2") (pinfunction "2_2") (pintype "passive"))
      (node (ref "C7") (pin "2") (pinfunction "2_2") (pintype "passive"))
      (node (ref "CONTRAST") (pin "1") (pinfunction "CCW_1") (pintype "passive"))
      (node (ref "IC1") (pin "18") (pinfunction "AVCC_18") (pintype "power_in"))
      (node (ref "IC1") (pin "20") (pinfunction "AREF_20") (pintype "passive"))
      (node (ref "IC1") (pin "4") (pinfunction "VCC_4") (pintype "power_in"))
      (node (ref "IC1") (pin "6") (pinfunction "VCC_6") (pintype "power_in"))
      (node (ref "IC2") (pin "3") (pinfunction "VO_3") (pintype "passive"))
      (node (ref "IC3") (pin "8") (pinfunction "VCC_8") (pintype "passive"))
      (node (ref "IC4") (pin "14") (pinfunction "VCC_14") (pintype "power_in"))
      (node (ref "JP0") (pin "2") (pinfunction "2_2") (pintype "passive"))
      (node (ref "LCD") (pin "2") (pinfunction "VDD_2") (pintype "power_in"))
      (node (ref "PWR") (pin "A") (pinfunction "A_A") (pintype "passive"))
      (node (ref "R12") (pin "2") (pinfunction "2_2") (pintype "passive"))
      (node (ref "R15") (pin "1") (pinfunction "1_1") (pintype "passive"))
      (node (ref "R16") (pin "1") (pinfunction "1_1") (pintype "passive"))
      (node (ref "R8") (pin "2") (pinfunction "2_2") (pintype "passive"))
      (node (ref "U$34") (pin "2") (pinfunction "VCC_2") (pintype "power_in"))
    )
    (net (code "65") (name "unconnected-(CLK_IN-PadRING_NC)") (class "Default")
      (node (ref "CLK_IN") (pin "RING_NC") (pinfunction "RING_NC_RING_NC") (pintype "bidirectional"))
    )
    (net (code "66") (name "unconnected-(CLK_IN-PadTIP_NC)") (class "Default")
      (node (ref "CLK_IN") (pin "TIP_NC") (pinfunction "TIP_NC_TIP_NC") (pintype "bidirectional"))
    )
    (net (code "67") (name "unconnected-(IC1-ADC6-Pad19)") (class "Default")
      (node (ref "IC1") (pin "19") (pinfunction "ADC6_19") (pintype "bidirectional"))
    )
    (net (code "68") (name "unconnected-(IC1-ADC7-Pad22)") (class "Default")
      (node (ref "IC1") (pin "22") (pinfunction "ADC7_22") (pintype "bidirectional"))
    )
    (net (code "69") (name "unconnected-(IC1-PB2(SS{slash}OC1B)-Pad14)") (class "Default")
      (node (ref "IC1") (pin "14") (pinfunction "PB2(SS/OC1B)_14") (pintype "bidirectional"))
    )
    (net (code "70") (name "unconnected-(LCD-DB0-Pad7)") (class "Default")
      (node (ref "LCD") (pin "7") (pinfunction "DB0_7") (pintype "bidirectional"))
    )
    (net (code "71") (name "unconnected-(LCD-DB1-Pad8)") (class "Default")
      (node (ref "LCD") (pin "8") (pinfunction "DB1_8") (pintype "bidirectional"))
    )
    (net (code "72") (name "unconnected-(LCD-DB2-Pad9)") (class "Default")
      (node (ref "LCD") (pin "9") (pinfunction "DB2_9") (pintype "bidirectional"))
    )
    (net (code "73") (name "unconnected-(LCD-DB3-Pad10)") (class "Default")
      (node (ref "LCD") (pin "10") (pinfunction "DB3_10") (pintype "bidirectional"))
    )
    (net (code "74") (name "unconnected-(ONOFF-PadP$1)") (class "Default")
      (node (ref "ONOFF") (pin "P$1") (pinfunction "P$1_P$1") (pintype "bidirectional"))
    )
    (net (code "75") (name "unconnected-(ONOFF-PadP$6)") (class "Default")
      (node (ref "ONOFF") (pin "P$6") (pinfunction "P$6_P$6") (pintype "bidirectional"))
    )
    (net (code "76") (name "unconnected-(OUT_A-PadRING_NC)") (class "Default")
      (node (ref "OUT_A") (pin "RING_NC") (pinfunction "RING_NC_RING_NC") (pintype "bidirectional"))
    )
    (net (code "77") (name "unconnected-(OUT_A-PadTIP_NC)") (class "Default")
      (node (ref "OUT_A") (pin "TIP_NC") (pinfunction "TIP_NC_TIP_NC") (pintype "bidirectional"))
    )
    (net (code "78") (name "unconnected-(OUT_B-PadRING_NC)") (class "Default")
      (node (ref "OUT_B") (pin "RING_NC") (pinfunction "RING_NC_RING_NC") (pintype "bidirectional"))
    )
    (net (code "79") (name "unconnected-(OUT_B-PadTIP_NC)") (class "Default")
      (node (ref "OUT_B") (pin "TIP_NC") (pinfunction "TIP_NC_TIP_NC") (pintype "bidirectional"))
    )
    (net (code "80") (name "unconnected-(OUT_C-PadRING_NC)") (class "Default")
      (node (ref "OUT_C") (pin "RING_NC") (pinfunction "RING_NC_RING_NC") (pintype "bidirectional"))
    )
    (net (code "81") (name "unconnected-(OUT_C-PadTIP_NC)") (class "Default")
      (node (ref "OUT_C") (pin "TIP_NC") (pinfunction "TIP_NC_TIP_NC") (pintype "bidirectional"))
    )
    (net (code "82") (name "unconnected-(OUT_D-PadRING_NC)") (class "Default")
      (node (ref "OUT_D") (pin "RING_NC") (pinfunction "RING_NC_RING_NC") (pintype "bidirectional"))
    )
    (net (code "83") (name "unconnected-(OUT_D-PadTIP_NC)") (class "Default")
      (node (ref "OUT_D") (pin "TIP_NC") (pinfunction "TIP_NC_TIP_NC") (pintype "bidirectional"))
    )
  )
)
